# PCB_Vienna.net
KiCad netlist of a schematic drawn in EAGLE
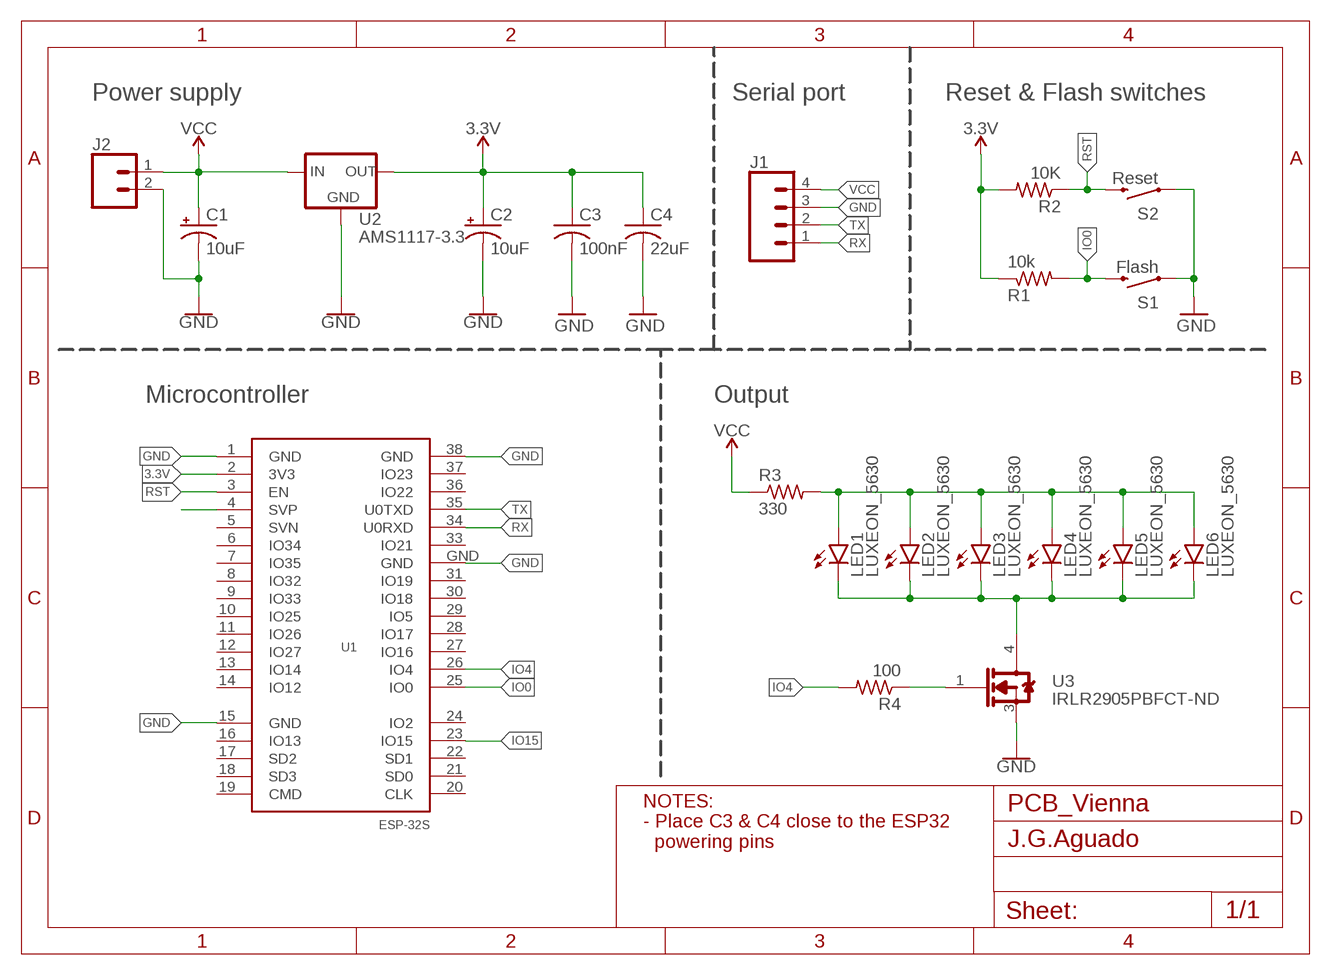
[diagram p0: schematic, sheet 1]

(export (version "E")
  (design (tool "Eeschema 10.0.6"))
  (components
    (comp (ref "C1")
      (value "10uF")
      (footprint "eagle-import:A_3216-18R")
      (libsource (lib "eagle-import") (part "CPOL-USA/3216-18R"))
    )
    (comp (ref "C2")
      (value "10uF")
      (footprint "eagle-import:A_3216-18R")
      (libsource (lib "eagle-import") (part "CPOL-USA/3216-18R"))
    )
    (comp (ref "C3")
      (value "100nF")
      (footprint "eagle-import:C1206")
      (libsource (lib "eagle-import") (part "C-USC1206"))
    )
    (comp (ref "C4")
      (value "22uF")
      (footprint "eagle-import:C1206")
      (libsource (lib "eagle-import") (part "C-USC1206"))
    )
    (comp (ref "J1")
      (value "CONN_04SMD_RA_FEMALE")
      (footprint "eagle-import:1X04_SMD_RA_FEMALE")
      (libsource (lib "eagle-import") (part "CONN_04SMD_RA_FEMALE"))
    )
    (comp (ref "J2")
      (value "CONN_02-JST-2MM-SMT")
      (footprint "eagle-import:JST-2-SMD")
      (libsource (lib "eagle-import") (part "CONN_02-JST-2MM-SMT"))
    )
    (comp (ref "LED1")
      (value "LUXEON_5630")
      (footprint "eagle-import:LUXEON_5630")
      (libsource (lib "eagle-import") (part "LUXEON_5630"))
    )
    (comp (ref "LED2")
      (value "LUXEON_5630")
      (footprint "eagle-import:LUXEON_5630")
      (libsource (lib "eagle-import") (part "LUXEON_5630"))
    )
    (comp (ref "LED3")
      (value "LUXEON_5630")
      (footprint "eagle-import:LUXEON_5630")
      (libsource (lib "eagle-import") (part "LUXEON_5630"))
    )
    (comp (ref "LED4")
      (value "LUXEON_5630")
      (footprint "eagle-import:LUXEON_5630")
      (libsource (lib "eagle-import") (part "LUXEON_5630"))
    )
    (comp (ref "LED5")
      (value "LUXEON_5630")
      (footprint "eagle-import:LUXEON_5630")
      (libsource (lib "eagle-import") (part "LUXEON_5630"))
    )
    (comp (ref "LED6")
      (value "LUXEON_5630")
      (footprint "eagle-import:LUXEON_5630")
      (libsource (lib "eagle-import") (part "LUXEON_5630"))
    )
    (comp (ref "R1")
      (value "10k")
      (footprint "eagle-import:M1206")
      (libsource (lib "eagle-import") (part "R-US_M1206"))
    )
    (comp (ref "R2")
      (value "10K")
      (footprint "eagle-import:M1206")
      (libsource (lib "eagle-import") (part "R-US_M1206"))
    )
    (comp (ref "R3")
      (value "330")
      (footprint "eagle-import:M1206")
      (libsource (lib "eagle-import") (part "R-US_M1206"))
    )
    (comp (ref "R4")
      (value "100")
      (footprint "eagle-import:M1206")
      (libsource (lib "eagle-import") (part "R-US_M1206"))
    )
    (comp (ref "S1")
      (value "Flash")
      (footprint "eagle-import:TACTILE_SWITCH_TALL")
      (libsource (lib "eagle-import") (part "SWITCH-MOMENTARY-2SMD-4"))
    )
    (comp (ref "S2")
      (value "Reset")
      (footprint "eagle-import:TACTILE_SWITCH_TALL")
      (libsource (lib "eagle-import") (part "SWITCH-MOMENTARY-2SMD-4"))
    )
    (comp (ref "U1")
      (value "ESP-32S")
      (footprint "eagle-import:ESP-32S")
      (libsource (lib "eagle-import") (part "ESP-32S"))
    )
    (comp (ref "U2")
      (value "AMS1117-3.3")
      (footprint "eagle-import:SOT223")
      (libsource (lib "eagle-import") (part "V_REG_LD1117VXXLD1117-SMD"))
    )
    (comp (ref "U3")
      (value "IRLR2905TRPBF")
      (footprint "eagle-import:INFINEON_TECHNOLOGIES_IRLR2905TRPBF_0")
      (fields
        (field (name "DIGIKEY_PART_NUMBER") "IRLR2905PBFCT-ND")
        (field (name "MF") "Infineon Technologies")
        (field (name "MOUSER_PART_NUMBER") "942-IRLR2905TRPBF")
      )
      (libsource (lib "eagle-import") (part "INFINEON_TECHNOLOGIES_IRLR2905TRPBFINFINEON_TECHNOLOGIES_IRLR2905TRPBF_0_0"))
    )
  )
  (nets
    (net (code "1") (name "3.3V") (class "Default")
      (node (ref "C2") (pin "+") (pinfunction "+_+") (pintype "passive"))
      (node (ref "C3") (pin "1") (pinfunction "1_1") (pintype "passive"))
      (node (ref "C4") (pin "1") (pinfunction "1_1") (pintype "passive"))
      (node (ref "R1") (pin "1") (pinfunction "1_1") (pintype "passive"))
      (node (ref "R2") (pin "2") (pinfunction "2_2") (pintype "passive"))
      (node (ref "U1") (pin "2") (pinfunction "3V3_2") (pintype "power_in"))
      (node (ref "U2") (pin "2") (pinfunction "OUT_2") (pintype "passive"))
    )
    (net (code "2") (name "GND") (class "Default")
      (node (ref "C1") (pin "-") (pinfunction "-_-") (pintype "passive"))
      (node (ref "C2") (pin "-") (pinfunction "-_-") (pintype "passive"))
      (node (ref "C3") (pin "2") (pinfunction "2_2") (pintype "passive"))
      (node (ref "C4") (pin "2") (pinfunction "2_2") (pintype "passive"))
      (node (ref "J1") (pin "3") (pinfunction "3_3") (pintype "passive"))
      (node (ref "J2") (pin "2") (pinfunction "1_2") (pintype "passive"))
      (node (ref "S1") (pin "A2") (pinfunction "1_A2") (pintype "passive"))
      (node (ref "S2") (pin "A2") (pinfunction "1_A2") (pintype "passive"))
      (node (ref "U1") (pin "1") (pinfunction "GND_1") (pintype "power_in"))
      (node (ref "U1") (pin "15") (pinfunction "GND_15") (pintype "power_in"))
      (node (ref "U1") (pin "38") (pinfunction "GND_38") (pintype "power_in"))
      (node (ref "U1") (pin "GND") (pinfunction "GND_GND") (pintype "power_in"))
      (node (ref "U2") (pin "1") (pinfunction "GND_1") (pintype "input"))
      (node (ref "U3") (pin "3") (pinfunction "SOURCE_3") (pintype "passive"))
    )
    (net (code "3") (name "IO0") (class "Default")
      (node (ref "R1") (pin "2") (pinfunction "2_2") (pintype "passive"))
      (node (ref "S1") (pin "B2") (pinfunction "2_B2") (pintype "passive"))
      (node (ref "U1") (pin "25") (pinfunction "IO0_25") (pintype "bidirectional"))
    )
    (net (code "4") (name "IO4") (class "Default")
      (node (ref "R4") (pin "2") (pinfunction "2_2") (pintype "passive"))
      (node (ref "U1") (pin "26") (pinfunction "IO4_26") (pintype "bidirectional"))
    )
    (net (code "5") (name "IO15") (class "Default")
      (node (ref "U1") (pin "23") (pinfunction "IO15_23") (pintype "bidirectional"))
    )
    (net (code "6") (name "Net-(LED1-A)") (class "Default")
      (node (ref "LED1") (pin "2") (pinfunction "A_2") (pintype "passive"))
      (node (ref "LED2") (pin "2") (pinfunction "A_2") (pintype "passive"))
      (node (ref "LED3") (pin "2") (pinfunction "A_2") (pintype "passive"))
      (node (ref "LED4") (pin "2") (pinfunction "A_2") (pintype "passive"))
      (node (ref "LED5") (pin "2") (pinfunction "A_2") (pintype "passive"))
      (node (ref "LED6") (pin "2") (pinfunction "A_2") (pintype "passive"))
      (node (ref "R3") (pin "2") (pinfunction "2_2") (pintype "passive"))
    )
    (net (code "7") (name "Net-(U3-DRAIN)") (class "Default")
      (node (ref "LED1") (pin "1@1") (pinfunction "C_1@1") (pintype "passive"))
      (node (ref "LED1") (pin "1@2") (pinfunction "C_1@2") (pintype "passive"))
      (node (ref "LED2") (pin "1@1") (pinfunction "C_1@1") (pintype "passive"))
      (node (ref "LED2") (pin "1@2") (pinfunction "C_1@2") (pintype "passive"))
      (node (ref "LED3") (pin "1@1") (pinfunction "C_1@1") (pintype "passive"))
      (node (ref "LED3") (pin "1@2") (pinfunction "C_1@2") (pintype "passive"))
      (node (ref "LED4") (pin "1@1") (pinfunction "C_1@1") (pintype "passive"))
      (node (ref "LED4") (pin "1@2") (pinfunction "C_1@2") (pintype "passive"))
      (node (ref "LED5") (pin "1@1") (pinfunction "C_1@1") (pintype "passive"))
      (node (ref "LED5") (pin "1@2") (pinfunction "C_1@2") (pintype "passive"))
      (node (ref "LED6") (pin "1@1") (pinfunction "C_1@1") (pintype "passive"))
      (node (ref "LED6") (pin "1@2") (pinfunction "C_1@2") (pintype "passive"))
      (node (ref "U3") (pin "4") (pinfunction "DRAIN_4") (pintype "passive"))
    )
    (net (code "8") (name "Net-(U3-GATE)") (class "Default")
      (node (ref "R4") (pin "1") (pinfunction "1_1") (pintype "passive"))
      (node (ref "U3") (pin "1") (pinfunction "GATE_1") (pintype "passive"))
    )
    (net (code "9") (name "RST") (class "Default")
      (node (ref "R2") (pin "1") (pinfunction "1_1") (pintype "passive"))
      (node (ref "S2") (pin "B2") (pinfunction "2_B2") (pintype "passive"))
      (node (ref "U1") (pin "3") (pinfunction "EN_3") (pintype "input"))
    )
    (net (code "10") (name "RX") (class "Default")
      (node (ref "J1") (pin "1") (pinfunction "1_1") (pintype "passive"))
      (node (ref "U1") (pin "34") (pinfunction "U0RXD_34") (pintype "bidirectional"))
    )
    (net (code "11") (name "TX") (class "Default")
      (node (ref "J1") (pin "2") (pinfunction "2_2") (pintype "passive"))
      (node (ref "U1") (pin "35") (pinfunction "U0TXD_35") (pintype "bidirectional"))
    )
    (net (code "12") (name "VCC") (class "Default")
      (node (ref "C1") (pin "+") (pinfunction "+_+") (pintype "passive"))
      (node (ref "J1") (pin "4") (pinfunction "4_4") (pintype "passive"))
      (node (ref "J2") (pin "1") (pinfunction "2_1") (pintype "passive"))
      (node (ref "R3") (pin "1") (pinfunction "1_1") (pintype "passive"))
      (node (ref "U2") (pin "3") (pinfunction "IN_3") (pintype "input"))
    )
    (net (code "13") (name "unconnected-(U1-CLK-Pad20)") (class "Default")
      (node (ref "U1") (pin "20") (pinfunction "CLK_20") (pintype "bidirectional"))
    )
    (net (code "14") (name "unconnected-(U1-CMD-Pad19)") (class "Default")
      (node (ref "U1") (pin "19") (pinfunction "CMD_19") (pintype "bidirectional"))
    )
    (net (code "15") (name "unconnected-(U1-IO2-Pad24)") (class "Default")
      (node (ref "U1") (pin "24") (pinfunction "IO2_24") (pintype "bidirectional"))
    )
    (net (code "16") (name "unconnected-(U1-IO5-Pad29)") (class "Default")
      (node (ref "U1") (pin "29") (pinfunction "IO5_29") (pintype "bidirectional"))
    )
    (net (code "17") (name "unconnected-(U1-IO12-Pad14)") (class "Default")
      (node (ref "U1") (pin "14") (pinfunction "IO12_14") (pintype "bidirectional"))
    )
    (net (code "18") (name "unconnected-(U1-IO13-Pad16)") (class "Default")
      (node (ref "U1") (pin "16") (pinfunction "IO13_16") (pintype "bidirectional"))
    )
    (net (code "19") (name "unconnected-(U1-IO14-Pad13)") (class "Default")
      (node (ref "U1") (pin "13") (pinfunction "IO14_13") (pintype "bidirectional"))
    )
    (net (code "20") (name "unconnected-(U1-IO16-Pad27)") (class "Default")
      (node (ref "U1") (pin "27") (pinfunction "IO16_27") (pintype "bidirectional"))
    )
    (net (code "21") (name "unconnected-(U1-IO17-Pad28)") (class "Default")
      (node (ref "U1") (pin "28") (pinfunction "IO17_28") (pintype "bidirectional"))
    )
    (net (code "22") (name "unconnected-(U1-IO18-Pad30)") (class "Default")
      (node (ref "U1") (pin "30") (pinfunction "IO18_30") (pintype "bidirectional"))
    )
    (net (code "23") (name "unconnected-(U1-IO19-Pad31)") (class "Default")
      (node (ref "U1") (pin "31") (pinfunction "IO19_31") (pintype "bidirectional"))
    )
    (net (code "24") (name "unconnected-(U1-IO21-Pad33)") (class "Default")
      (node (ref "U1") (pin "33") (pinfunction "IO21_33") (pintype "bidirectional"))
    )
    (net (code "25") (name "unconnected-(U1-IO22-Pad36)") (class "Default")
      (node (ref "U1") (pin "36") (pinfunction "IO22_36") (pintype "bidirectional"))
    )
    (net (code "26") (name "unconnected-(U1-IO23-Pad37)") (class "Default")
      (node (ref "U1") (pin "37") (pinfunction "IO23_37") (pintype "bidirectional"))
    )
    (net (code "27") (name "unconnected-(U1-IO25-Pad10)") (class "Default")
      (node (ref "U1") (pin "10") (pinfunction "IO25_10") (pintype "bidirectional"))
    )
    (net (code "28") (name "unconnected-(U1-IO26-Pad11)") (class "Default")
      (node (ref "U1") (pin "11") (pinfunction "IO26_11") (pintype "bidirectional"))
    )
    (net (code "29") (name "unconnected-(U1-IO27-Pad12)") (class "Default")
      (node (ref "U1") (pin "12") (pinfunction "IO27_12") (pintype "bidirectional"))
    )
    (net (code "30") (name "unconnected-(U1-IO32-Pad8)") (class "Default")
      (node (ref "U1") (pin "8") (pinfunction "IO32_8") (pintype "bidirectional"))
    )
    (net (code "31") (name "unconnected-(U1-IO33-Pad9)") (class "Default")
      (node (ref "U1") (pin "9") (pinfunction "IO33_9") (pintype "bidirectional"))
    )
    (net (code "32") (name "unconnected-(U1-IO34-Pad6)") (class "Default")
      (node (ref "U1") (pin "6") (pinfunction "IO34_6") (pintype "bidirectional"))
    )
    (net (code "33") (name "unconnected-(U1-IO35-Pad7)") (class "Default")
      (node (ref "U1") (pin "7") (pinfunction "IO35_7") (pintype "bidirectional"))
    )
    (net (code "34") (name "unconnected-(U1-SD0-Pad21)") (class "Default")
      (node (ref "U1") (pin "21") (pinfunction "SD0_21") (pintype "bidirectional"))
    )
    (net (code "35") (name "unconnected-(U1-SD1-Pad22)") (class "Default")
      (node (ref "U1") (pin "22") (pinfunction "SD1_22") (pintype "bidirectional"))
    )
    (net (code "36") (name "unconnected-(U1-SD2-Pad17)") (class "Default")
      (node (ref "U1") (pin "17") (pinfunction "SD2_17") (pintype "bidirectional"))
    )
    (net (code "37") (name "unconnected-(U1-SD3-Pad18)") (class "Default")
      (node (ref "U1") (pin "18") (pinfunction "SD3_18") (pintype "bidirectional"))
    )
    (net (code "38") (name "unconnected-(U1-SVN-Pad5)") (class "Default")
      (node (ref "U1") (pin "5") (pinfunction "SVN_5") (pintype "bidirectional"))
    )
    (net (code "39") (name "unconnected-(U1-SVP-Pad4)") (class "Default")
      (node (ref "U1") (pin "4") (pinfunction "SVP_4") (pintype "bidirectional"))
    )
  )
)
